# SCH_Christmas-Tree-1_2024-10-02.net
KiCad netlist of a schematic drawn in EasyEDA
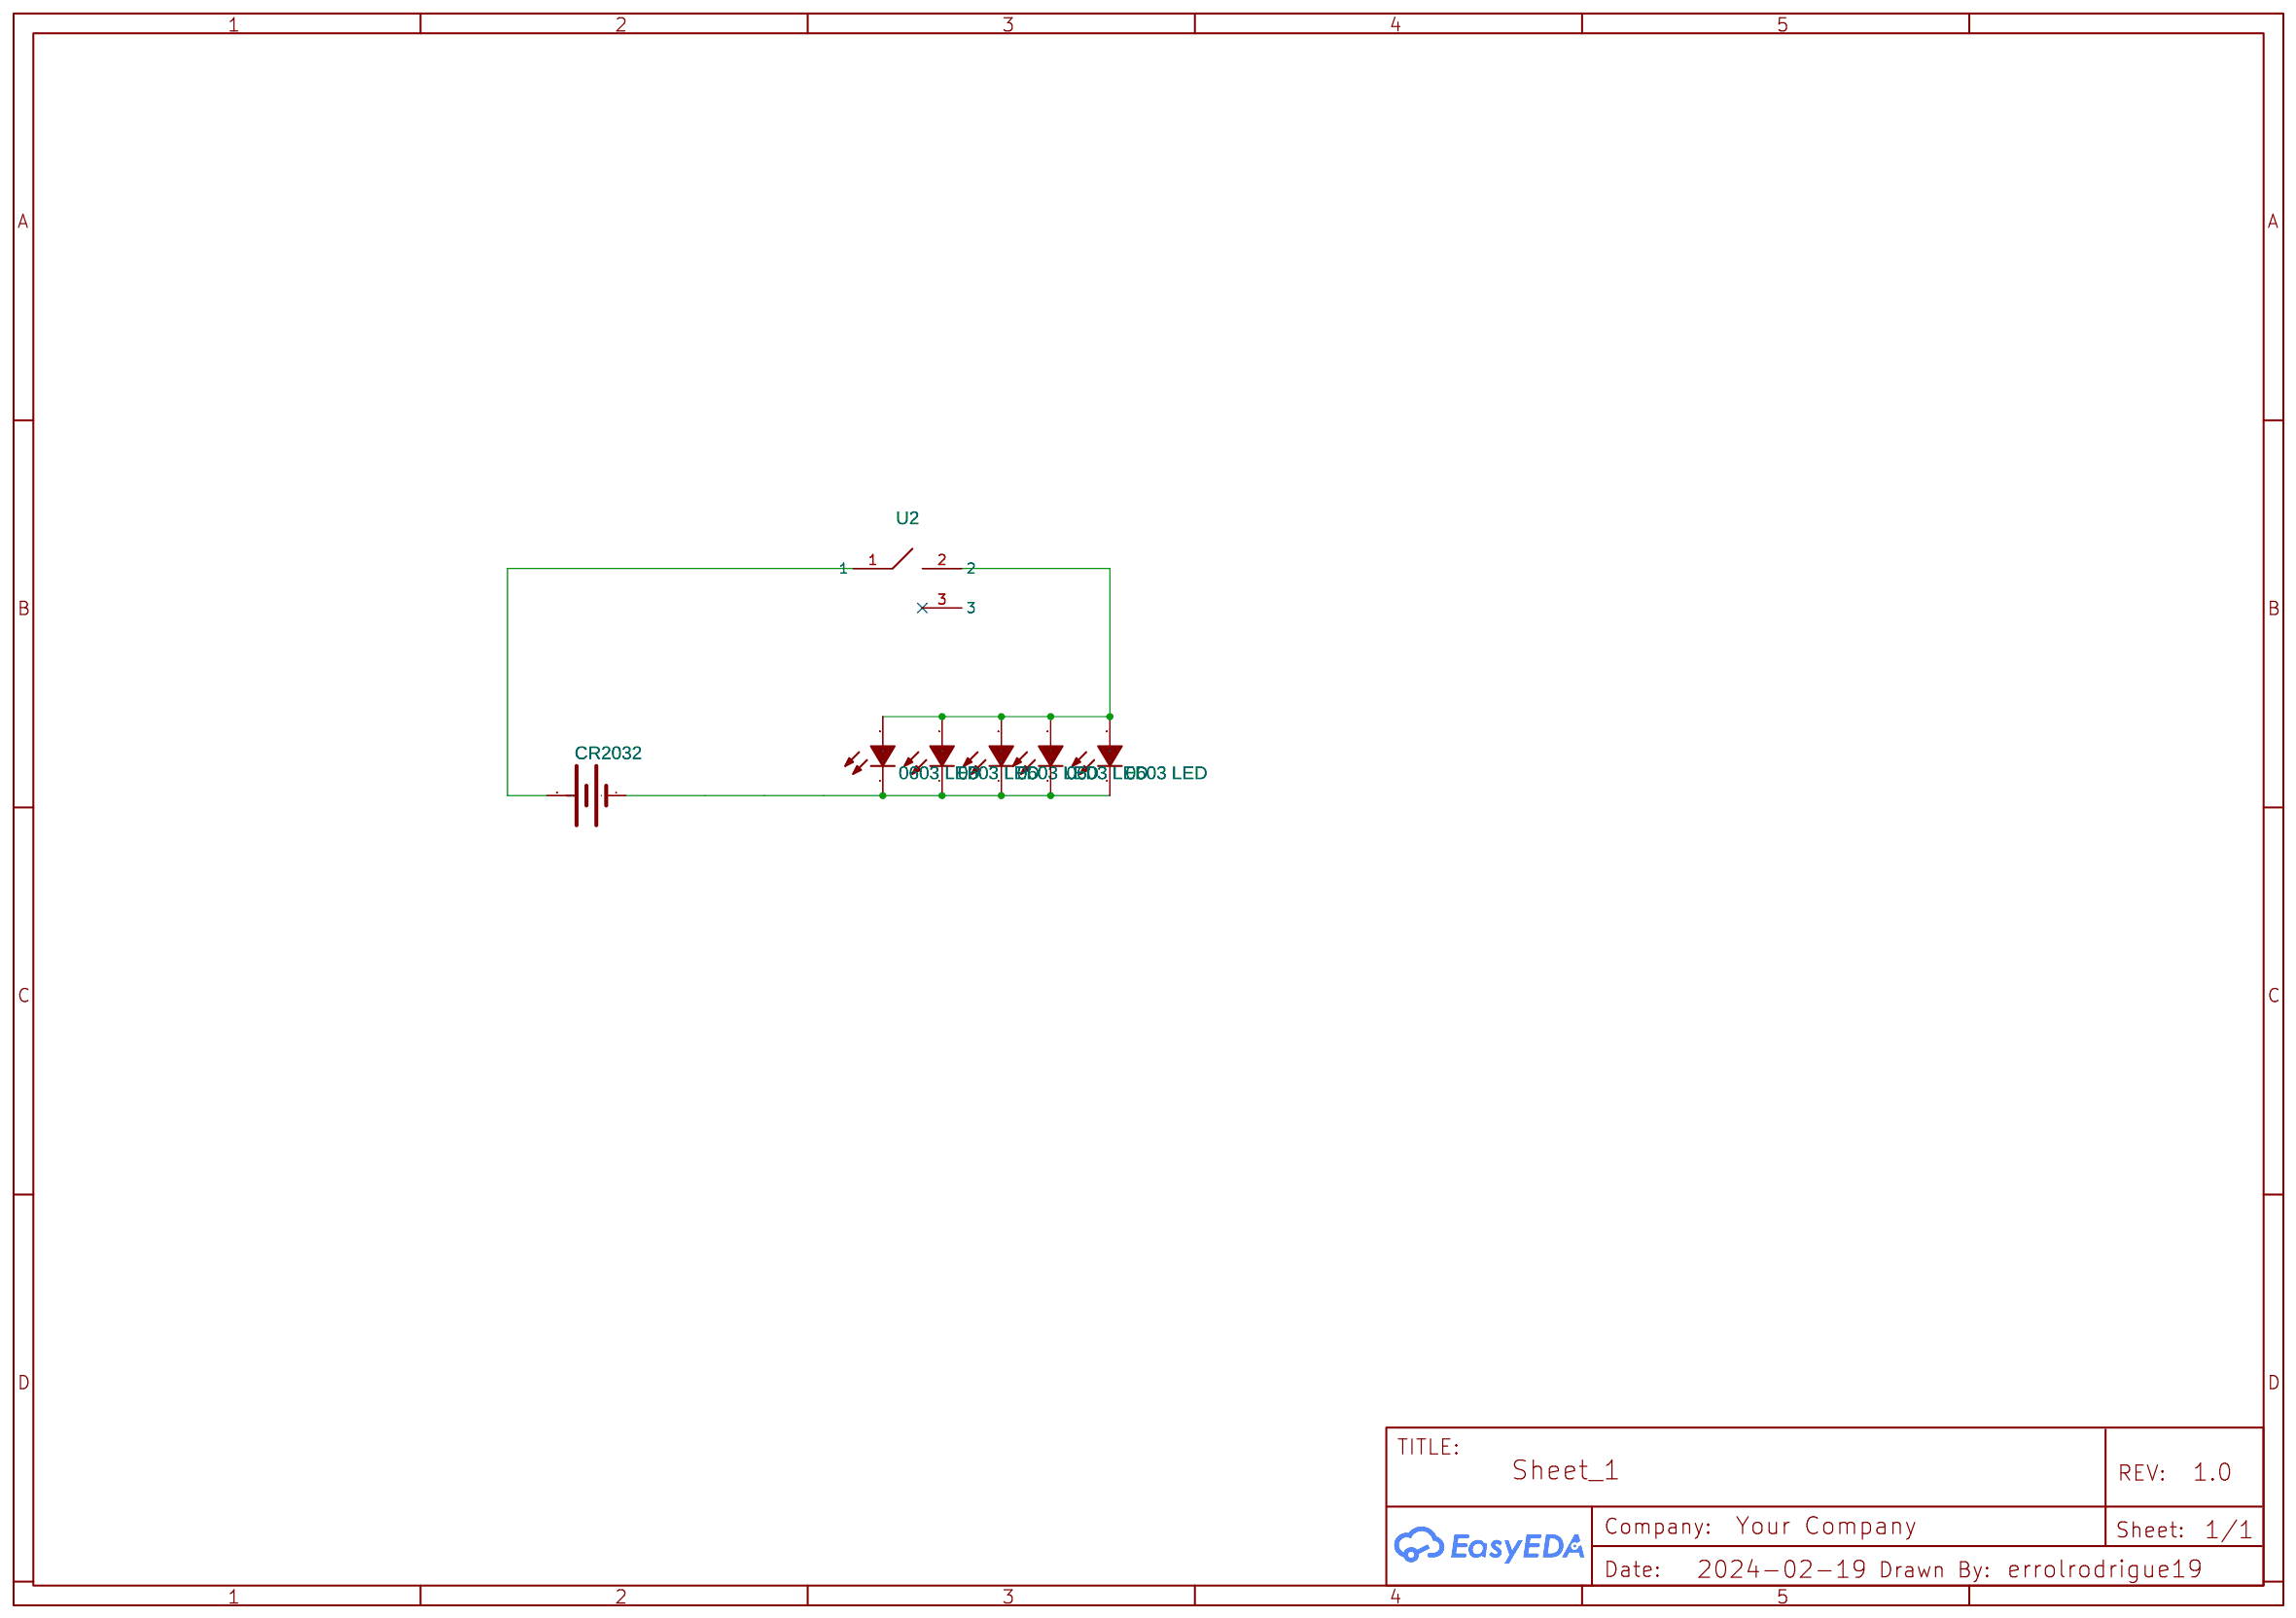
[diagram p0: schematic sheet]

(export (version "E")
  (design (tool "Eeschema 10.0.6"))
  (components
    (comp (ref "LED2")
      (value "0603 LED")
      (fields (field (name "Manufacturer Part") "LED-0603"))
      (libsource (lib "") (part "LED-0603"))
    )
    (comp (ref "LED3")
      (value "0603 LED")
      (fields (field (name "Manufacturer Part") "LED-0603"))
      (libsource (lib "") (part "LED-0603"))
    )
    (comp (ref "LED4")
      (value "0603 LED")
      (fields (field (name "Manufacturer Part") "LED-0603"))
      (libsource (lib "") (part "LED-0603"))
    )
    (comp (ref "LED7")
      (value "0603 LED")
      (fields (field (name "Manufacturer Part") "LED-0603"))
      (libsource (lib "") (part "LED-0603"))
    )
    (comp (ref "LED8")
      (value "0603 LED")
      (fields (field (name "Manufacturer Part") "LED-0603"))
      (libsource (lib "") (part "LED-0603"))
    )
    (comp (ref "U1")
      (value "CR2032")
      (fields (field (name "Manufacturer Part") "CR2032-卧式贴片"))
      (libsource (lib "") (part "CR2032-卧式贴片"))
    )
    (comp (ref "U2") (value "拨键开关MSK-12C02") (libsource (lib "") (part "拨键开关MSK-12C02")))
  )
  (nets
    (net (code "1") (name "Net-(LED2-+)") (class "Default")
      (node (ref "LED2") (pin "2") (pinfunction "+_2") (pintype "input"))
      (node (ref "LED3") (pin "2") (pinfunction "+_2") (pintype "input"))
      (node (ref "LED4") (pin "2") (pinfunction "+_2") (pintype "input"))
      (node (ref "LED7") (pin "2") (pinfunction "+_2") (pintype "input"))
      (node (ref "LED8") (pin "2") (pinfunction "+_2") (pintype "input"))
      (node (ref "U2") (pin "2") (pinfunction "2_2") (pintype "unspecified"))
    )
    (net (code "2") (name "Net-(LED2--)") (class "Default")
      (node (ref "LED2") (pin "1") (pinfunction "-_1") (pintype "input"))
      (node (ref "LED3") (pin "1") (pinfunction "-_1") (pintype "input"))
      (node (ref "LED4") (pin "1") (pinfunction "-_1") (pintype "input"))
      (node (ref "LED7") (pin "1") (pinfunction "-_1") (pintype "input"))
      (node (ref "LED8") (pin "1") (pinfunction "-_1") (pintype "input"))
      (node (ref "U1") (pin "1") (pinfunction "-_1") (pintype "passive"))
    )
    (net (code "3") (name "Net-(U1-+)") (class "Default")
      (node (ref "U1") (pin "2") (pinfunction "+_2") (pintype "passive"))
      (node (ref "U2") (pin "1") (pinfunction "1_1") (pintype "unspecified"))
    )
    (net (code "4") (name "unconnected-(U2-Pad3)") (class "Default")
      (node (ref "U2") (pin "3") (pinfunction "3_3") (pintype "unspecified+no_connect"))
    )
  )
)
